# ATMEGA_328_Programmer.net
KiCad netlist of a schematic drawn in EAGLE
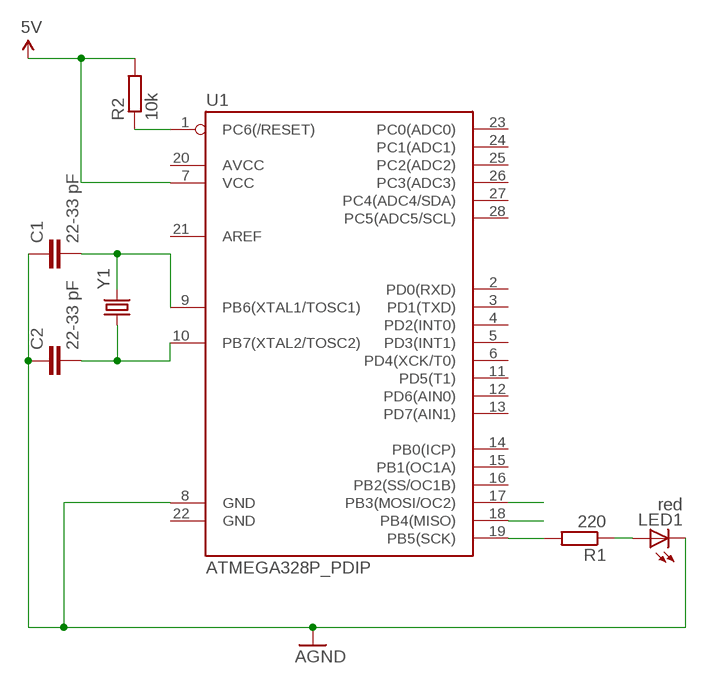
[diagram p0: schematic, sheet 1]

(export (version "E")
  (design (tool "Eeschema 10.0.6"))
  (components
    (comp (ref "C1")
      (value "22-33 pF")
      (footprint "eagle-import:AXIAL-5MM")
      (libsource (lib "eagle-import") (part "CAP_"))
    )
    (comp (ref "C2")
      (value "22-33 pF")
      (footprint "eagle-import:AXIAL-5MM")
      (libsource (lib "eagle-import") (part "CAP_"))
    )
    (comp (ref "LED1")
      (value "red")
      (footprint "eagle-import:LED3MM")
      (libsource (lib "eagle-import") (part "LED3MM"))
    )
    (comp (ref "R1")
      (value "220")
      (footprint "eagle-import:0204_7")
      (libsource (lib "eagle-import") (part "R-EU_0204/7"))
    )
    (comp (ref "R2")
      (value "10k")
      (footprint "eagle-import:0204_7")
      (libsource (lib "eagle-import") (part "R-EU_0204/7"))
    )
    (comp (ref "U1")
      (value "ATMEGA328P_PDIP")
      (footprint "eagle-import:DIL28-3")
      (libsource (lib "eagle-import") (part "ATMEGA328P_PDIP"))
    )
    (comp (ref "Y1")
      (value "CRYSTALHC49US")
      (footprint "eagle-import:HC49US")
      (libsource (lib "eagle-import") (part "CRYSTALHC49US"))
    )
  )
  (nets
    (net (code "1") (name "5V") (class "Default")
      (node (ref "R2") (pin "2") (pinfunction "2_2") (pintype "passive"))
      (node (ref "U1") (pin "7") (pinfunction "VCC_7") (pintype "bidirectional"))
    )
    (net (code "2") (name "AGND") (class "Default")
      (node (ref "C1") (pin "P$1") (pinfunction "1_P$1") (pintype "passive"))
      (node (ref "C2") (pin "P$1") (pinfunction "1_P$1") (pintype "passive"))
      (node (ref "LED1") (pin "K") (pinfunction "C_K") (pintype "passive"))
      (node (ref "U1") (pin "8") (pinfunction "GND_8") (pintype "bidirectional"))
    )
    (net (code "3") (name "Net-(C1-2)") (class "Default")
      (node (ref "C1") (pin "P$2") (pinfunction "2_P$2") (pintype "passive"))
      (node (ref "U1") (pin "9") (pinfunction "PB6(XTAL1/TOSC1)_9") (pintype "bidirectional"))
      (node (ref "Y1") (pin "2") (pinfunction "2_2") (pintype "passive"))
    )
    (net (code "4") (name "Net-(C2-2)") (class "Default")
      (node (ref "C2") (pin "P$2") (pinfunction "2_P$2") (pintype "passive"))
      (node (ref "U1") (pin "10") (pinfunction "PB7(XTAL2/TOSC2)_10") (pintype "bidirectional"))
      (node (ref "Y1") (pin "1") (pinfunction "1_1") (pintype "passive"))
    )
    (net (code "5") (name "Net-(LED1-PadA)") (class "Default")
      (node (ref "LED1") (pin "A") (pinfunction "A_A") (pintype "passive"))
      (node (ref "R1") (pin "1") (pinfunction "1_1") (pintype "passive"))
    )
    (net (code "6") (name "Net-(U1-PB5(SCK))") (class "Default")
      (node (ref "R1") (pin "2") (pinfunction "2_2") (pintype "passive"))
      (node (ref "U1") (pin "19") (pinfunction "PB5(SCK)_19") (pintype "bidirectional"))
    )
    (net (code "7") (name "Net-(U1-PC6({slash}RESET))") (class "Default")
      (node (ref "R2") (pin "1") (pinfunction "1_1") (pintype "passive"))
      (node (ref "U1") (pin "1") (pinfunction "PC6(/RESET)_1") (pintype "bidirectional"))
    )
    (net (code "8") (name "unconnected-(U1-AREF-Pad21)") (class "Default")
      (node (ref "U1") (pin "21") (pinfunction "AREF_21") (pintype "bidirectional"))
    )
    (net (code "9") (name "unconnected-(U1-AVCC-Pad20)") (class "Default")
      (node (ref "U1") (pin "20") (pinfunction "AVCC_20") (pintype "bidirectional"))
    )
    (net (code "10") (name "unconnected-(U1-GND-Pad22)") (class "Default")
      (node (ref "U1") (pin "22") (pinfunction "GND_22") (pintype "bidirectional"))
    )
    (net (code "11") (name "unconnected-(U1-PB0(ICP)-Pad14)") (class "Default")
      (node (ref "U1") (pin "14") (pinfunction "PB0(ICP)_14") (pintype "bidirectional"))
    )
    (net (code "12") (name "unconnected-(U1-PB1(OC1A)-Pad15)") (class "Default")
      (node (ref "U1") (pin "15") (pinfunction "PB1(OC1A)_15") (pintype "bidirectional"))
    )
    (net (code "13") (name "unconnected-(U1-PB2(SS{slash}OC1B)-Pad16)") (class "Default")
      (node (ref "U1") (pin "16") (pinfunction "PB2(SS/OC1B)_16") (pintype "bidirectional"))
    )
    (net (code "14") (name "unconnected-(U1-PB3(MOSI{slash}OC2)-Pad17)") (class "Default")
      (node (ref "U1") (pin "17") (pinfunction "PB3(MOSI/OC2)_17") (pintype "bidirectional"))
    )
    (net (code "15") (name "unconnected-(U1-PB4(MISO)-Pad18)") (class "Default")
      (node (ref "U1") (pin "18") (pinfunction "PB4(MISO)_18") (pintype "bidirectional"))
    )
    (net (code "16") (name "unconnected-(U1-PC0(ADC0)-Pad23)") (class "Default")
      (node (ref "U1") (pin "23") (pinfunction "PC0(ADC0)_23") (pintype "bidirectional"))
    )
    (net (code "17") (name "unconnected-(U1-PC1(ADC1)-Pad24)") (class "Default")
      (node (ref "U1") (pin "24") (pinfunction "PC1(ADC1)_24") (pintype "bidirectional"))
    )
    (net (code "18") (name "unconnected-(U1-PC2(ADC2)-Pad25)") (class "Default")
      (node (ref "U1") (pin "25") (pinfunction "PC2(ADC2)_25") (pintype "bidirectional"))
    )
    (net (code "19") (name "unconnected-(U1-PC3(ADC3)-Pad26)") (class "Default")
      (node (ref "U1") (pin "26") (pinfunction "PC3(ADC3)_26") (pintype "bidirectional"))
    )
    (net (code "20") (name "unconnected-(U1-PC4(ADC4{slash}SDA)-Pad27)") (class "Default")
      (node (ref "U1") (pin "27") (pinfunction "PC4(ADC4/SDA)_27") (pintype "bidirectional"))
    )
    (net (code "21") (name "unconnected-(U1-PC5(ADC5{slash}SCL)-Pad28)") (class "Default")
      (node (ref "U1") (pin "28") (pinfunction "PC5(ADC5/SCL)_28") (pintype "bidirectional"))
    )
    (net (code "22") (name "unconnected-(U1-PD0(RXD)-Pad2)") (class "Default")
      (node (ref "U1") (pin "2") (pinfunction "PD0(RXD)_2") (pintype "bidirectional"))
    )
    (net (code "23") (name "unconnected-(U1-PD1(TXD)-Pad3)") (class "Default")
      (node (ref "U1") (pin "3") (pinfunction "PD1(TXD)_3") (pintype "bidirectional"))
    )
    (net (code "24") (name "unconnected-(U1-PD2(INT0)-Pad4)") (class "Default")
      (node (ref "U1") (pin "4") (pinfunction "PD2(INT0)_4") (pintype "bidirectional"))
    )
    (net (code "25") (name "unconnected-(U1-PD3(INT1)-Pad5)") (class "Default")
      (node (ref "U1") (pin "5") (pinfunction "PD3(INT1)_5") (pintype "bidirectional"))
    )
    (net (code "26") (name "unconnected-(U1-PD4(XCK{slash}T0)-Pad6)") (class "Default")
      (node (ref "U1") (pin "6") (pinfunction "PD4(XCK/T0)_6") (pintype "bidirectional"))
    )
    (net (code "27") (name "unconnected-(U1-PD5(T1)-Pad11)") (class "Default")
      (node (ref "U1") (pin "11") (pinfunction "PD5(T1)_11") (pintype "bidirectional"))
    )
    (net (code "28") (name "unconnected-(U1-PD6(AIN0)-Pad12)") (class "Default")
      (node (ref "U1") (pin "12") (pinfunction "PD6(AIN0)_12") (pintype "bidirectional"))
    )
    (net (code "29") (name "unconnected-(U1-PD7(AIN1)-Pad13)") (class "Default")
      (node (ref "U1") (pin "13") (pinfunction "PD7(AIN1)_13") (pintype "bidirectional"))
    )
  )
)
